# Adafruit_MCP4725.net
KiCad netlist of a schematic drawn in EAGLE
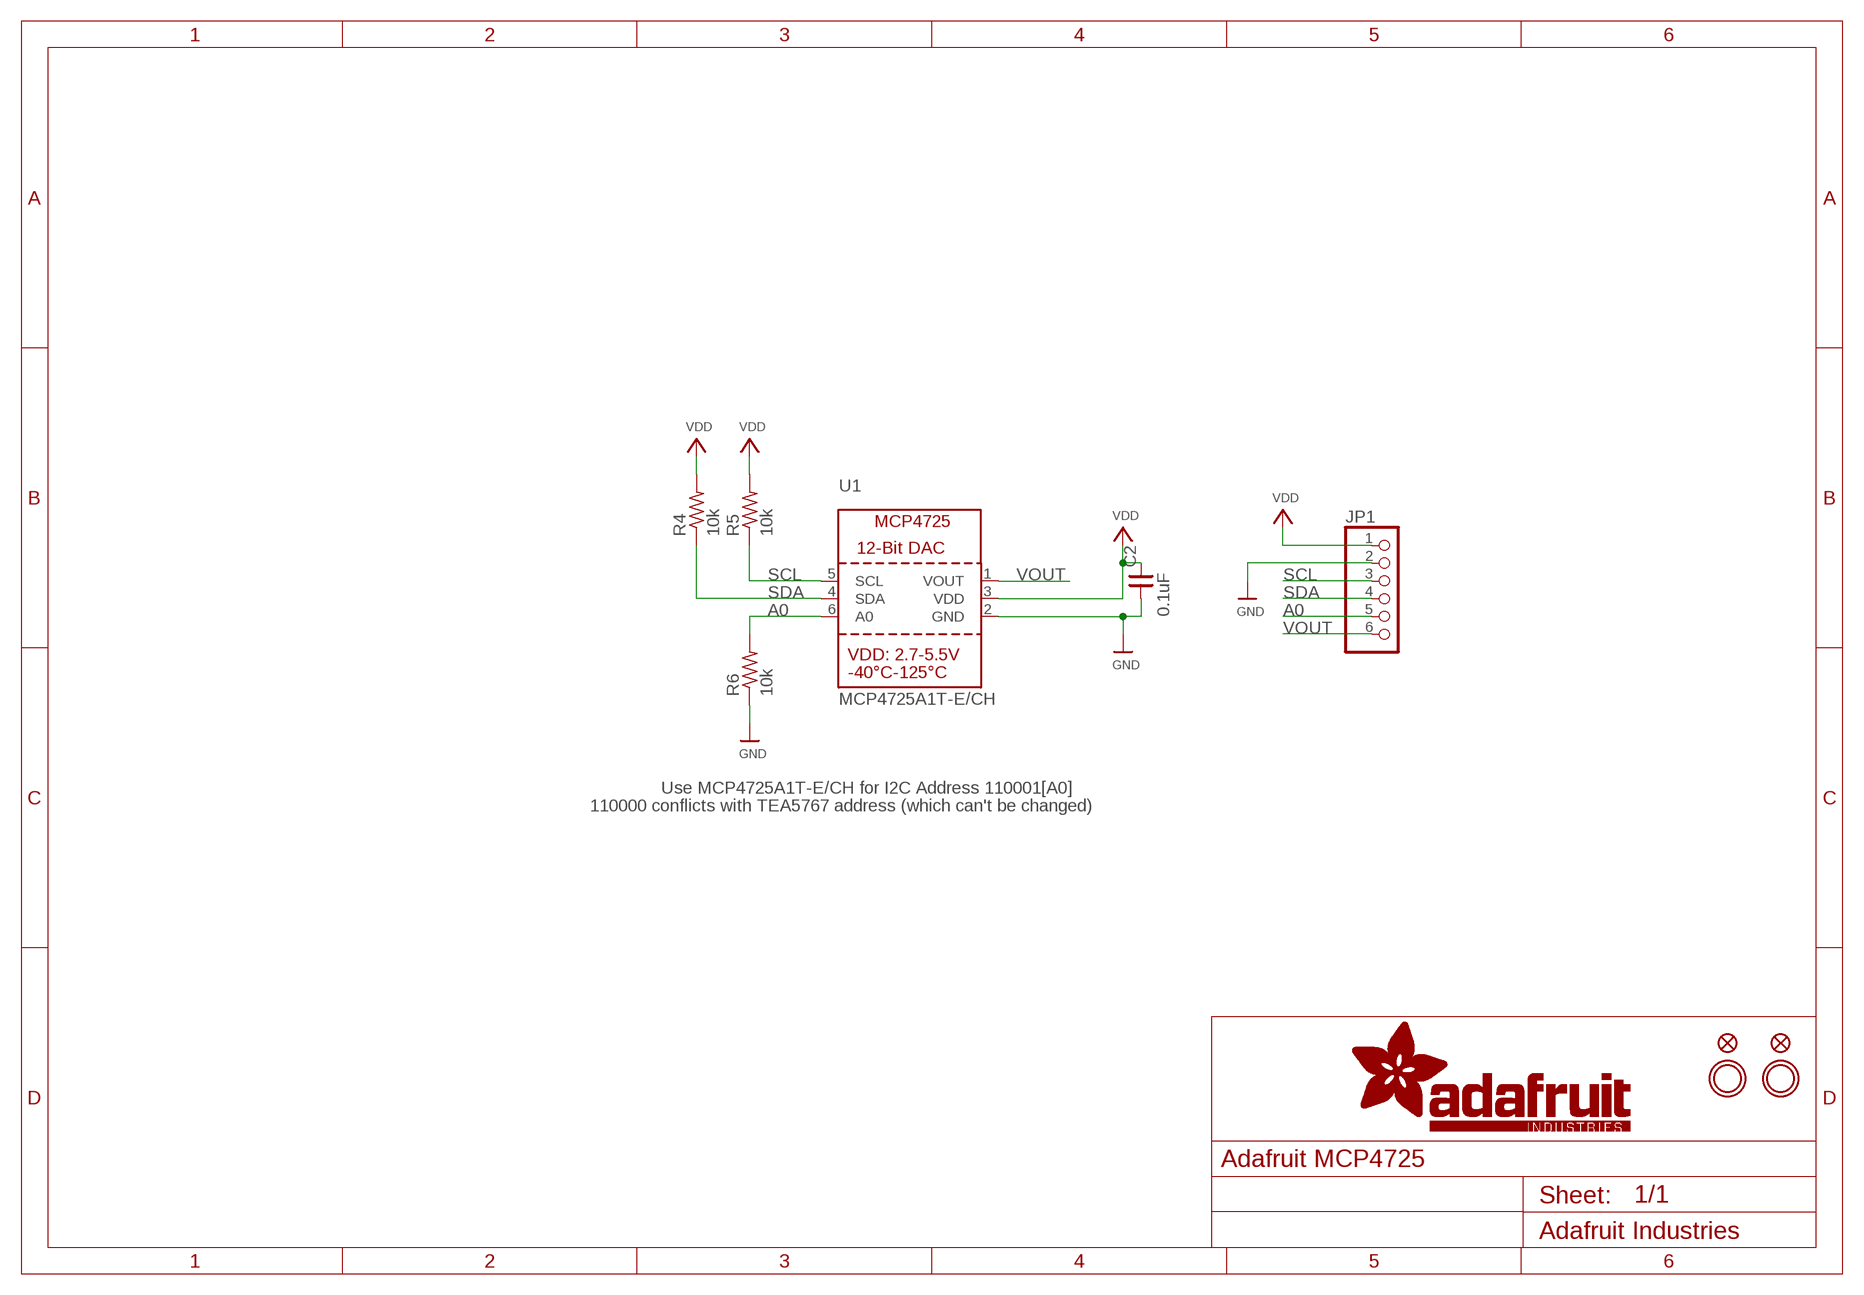
[diagram p0: schematic, sheet 1]

(export (version "E")
  (design (tool "Eeschema 10.0.6"))
  (components
    (comp (ref "C2")
      (value "0.1uF")
      (footprint "eagle-import:0805")
      (libsource (lib "eagle-import") (part "CNP-0805"))
    )
    (comp (ref "FID1")
      (value "FIDUCIAL\"\"")
      (footprint "eagle-import:FIDUCIAL_1MM")
      (libsource (lib "eagle-import") (part "FIDUCIAL{dblquote}{dblquote}"))
    )
    (comp (ref "FID2")
      (value "FIDUCIAL\"\"")
      (footprint "eagle-import:FIDUCIAL_1MM")
      (libsource (lib "eagle-import") (part "FIDUCIAL{dblquote}{dblquote}"))
    )
    (comp (ref "JP1")
      (value "HEADER-1X670MIL")
      (footprint "eagle-import:1X06_ROUND_70")
      (libsource (lib "eagle-import") (part "HEADER-1X670MIL"))
    )
    (comp (ref "R4")
      (value "10k")
      (footprint "eagle-import:R0805")
      (libsource (lib "eagle-import") (part "R-US_R0805"))
    )
    (comp (ref "R5")
      (value "10k")
      (footprint "eagle-import:R0805")
      (libsource (lib "eagle-import") (part "R-US_R0805"))
    )
    (comp (ref "R6")
      (value "10k")
      (footprint "eagle-import:R0805")
      (libsource (lib "eagle-import") (part "R-US_R0805"))
    )
    (comp (ref "U$7")
      (value "MOUNTINGHOLE2.5")
      (footprint "eagle-import:MOUNTINGHOLE_2.5_PLATED")
      (libsource (lib "eagle-import") (part "MOUNTINGHOLE2.5"))
    )
    (comp (ref "U$8")
      (value "MOUNTINGHOLE2.5")
      (footprint "eagle-import:MOUNTINGHOLE_2.5_PLATED")
      (libsource (lib "eagle-import") (part "MOUNTINGHOLE2.5"))
    )
    (comp (ref "U1")
      (value "MCP4725A1T-E/CH")
      (footprint "eagle-import:SOT23-6")
      (libsource (lib "eagle-import") (part "DAC_MCP4725"))
    )
  )
  (nets
    (net (code "1") (name "/A0") (class "Default")
      (node (ref "JP1") (pin "5") (pinfunction "5_5") (pintype "passive"))
      (node (ref "R6") (pin "2") (pinfunction "2_2") (pintype "passive"))
      (node (ref "U1") (pin "6") (pinfunction "A0_6") (pintype "input"))
    )
    (net (code "2") (name "/SCL") (class "Default")
      (node (ref "JP1") (pin "3") (pinfunction "3_3") (pintype "passive"))
      (node (ref "R5") (pin "1") (pinfunction "1_1") (pintype "passive"))
      (node (ref "U1") (pin "5") (pinfunction "SCL_5") (pintype "bidirectional"))
    )
    (net (code "3") (name "/SDA") (class "Default")
      (node (ref "JP1") (pin "4") (pinfunction "4_4") (pintype "passive"))
      (node (ref "R4") (pin "1") (pinfunction "1_1") (pintype "passive"))
      (node (ref "U1") (pin "4") (pinfunction "SDA_4") (pintype "bidirectional"))
    )
    (net (code "4") (name "/VOUT") (class "Default")
      (node (ref "JP1") (pin "6") (pinfunction "6_6") (pintype "passive"))
      (node (ref "U1") (pin "1") (pinfunction "VOUT_1") (pintype "output"))
    )
    (net (code "5") (name "GND") (class "Default")
      (node (ref "C2") (pin "1") (pinfunction "1_1") (pintype "passive"))
      (node (ref "JP1") (pin "2") (pinfunction "2_2") (pintype "passive"))
      (node (ref "R6") (pin "1") (pinfunction "1_1") (pintype "passive"))
      (node (ref "U1") (pin "2") (pinfunction "GND_2") (pintype "power_in"))
    )
    (net (code "6") (name "VDD") (class "Default")
      (node (ref "C2") (pin "2") (pinfunction "2_2") (pintype "passive"))
      (node (ref "JP1") (pin "1") (pinfunction "1_1") (pintype "passive"))
      (node (ref "R4") (pin "2") (pinfunction "2_2") (pintype "passive"))
      (node (ref "R5") (pin "2") (pinfunction "2_2") (pintype "passive"))
      (node (ref "U1") (pin "3") (pinfunction "VDD_3") (pintype "power_in"))
    )
  )
)
